# Softkey-bar.net
KiCad netlist of a schematic drawn in EAGLE
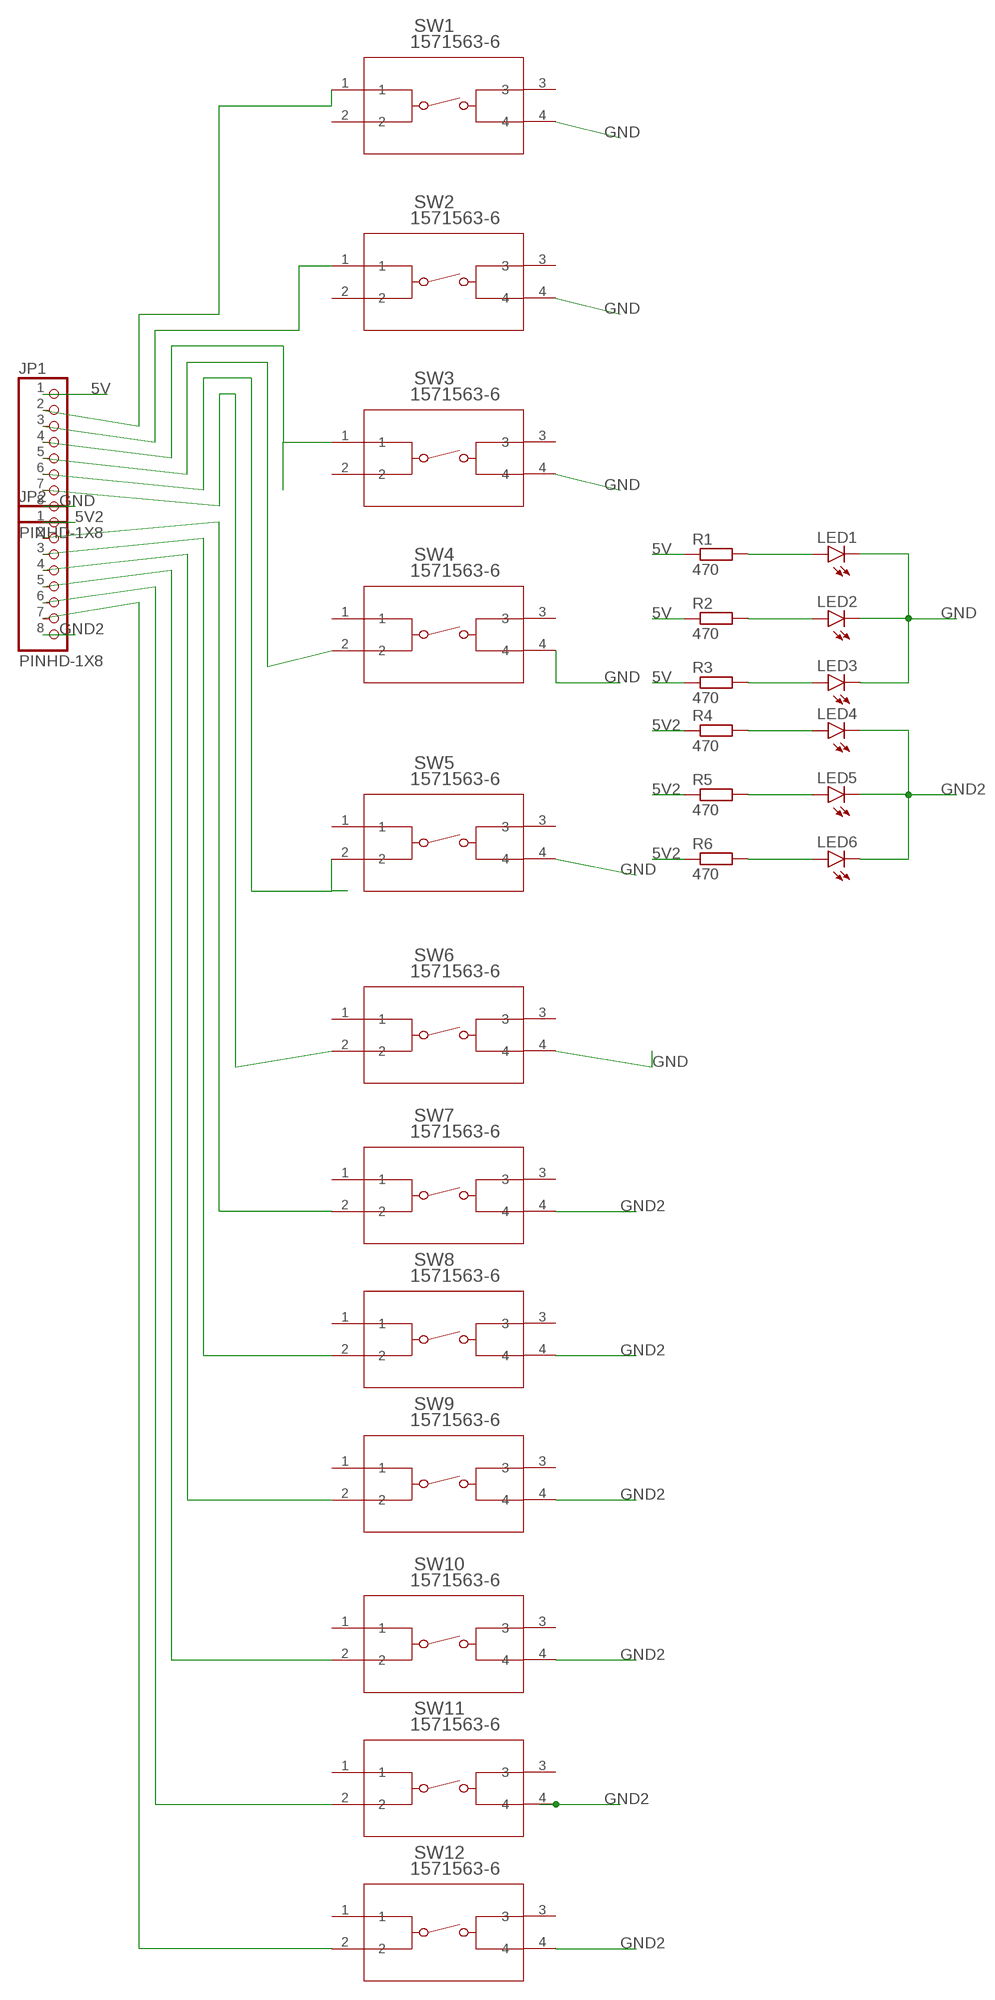
[diagram p0: schematic, sheet 1]

(export (version "E")
  (design (tool "Eeschema 10.0.6"))
  (components
    (comp (ref "JP1")
      (value "PINHD-1X8")
      (footprint "eagle-import:1X08")
      (libsource (lib "eagle-import") (part "PINHD-1X8"))
    )
    (comp (ref "JP2")
      (value "PINHD-1X8")
      (footprint "eagle-import:1X08")
      (libsource (lib "eagle-import") (part "PINHD-1X8"))
    )
    (comp (ref "LED1")
      (value "LEDCHIPLED_1206")
      (footprint "eagle-import:CHIPLED_1206")
      (libsource (lib "eagle-import") (part "LEDCHIPLED_1206"))
    )
    (comp (ref "LED2")
      (value "LEDCHIPLED_1206")
      (footprint "eagle-import:CHIPLED_1206")
      (libsource (lib "eagle-import") (part "LEDCHIPLED_1206"))
    )
    (comp (ref "LED3")
      (value "LEDCHIPLED_1206")
      (footprint "eagle-import:CHIPLED_1206")
      (libsource (lib "eagle-import") (part "LEDCHIPLED_1206"))
    )
    (comp (ref "LED4")
      (value "LEDCHIPLED_1206")
      (footprint "eagle-import:CHIPLED_1206")
      (libsource (lib "eagle-import") (part "LEDCHIPLED_1206"))
    )
    (comp (ref "LED5")
      (value "LEDCHIPLED_1206")
      (footprint "eagle-import:CHIPLED_1206")
      (libsource (lib "eagle-import") (part "LEDCHIPLED_1206"))
    )
    (comp (ref "LED6")
      (value "LEDCHIPLED_1206")
      (footprint "eagle-import:CHIPLED_1206")
      (libsource (lib "eagle-import") (part "LEDCHIPLED_1206"))
    )
    (comp (ref "R1")
      (value "470")
      (footprint "eagle-import:R0805")
      (libsource (lib "eagle-import") (part "R-EU_R0805"))
    )
    (comp (ref "R2")
      (value "470")
      (footprint "eagle-import:R0805")
      (libsource (lib "eagle-import") (part "R-EU_R0805"))
    )
    (comp (ref "R3")
      (value "470")
      (footprint "eagle-import:R0805")
      (libsource (lib "eagle-import") (part "R-EU_R0805"))
    )
    (comp (ref "R4")
      (value "470")
      (footprint "eagle-import:R0805")
      (libsource (lib "eagle-import") (part "R-EU_R0805"))
    )
    (comp (ref "R5")
      (value "470")
      (footprint "eagle-import:R0805")
      (libsource (lib "eagle-import") (part "R-EU_R0805"))
    )
    (comp (ref "R6")
      (value "470")
      (footprint "eagle-import:R0805")
      (libsource (lib "eagle-import") (part "R-EU_R0805"))
    )
    (comp (ref "SW1")
      (value "1571563-6")
      (footprint "eagle-import:SW4_1437565-E")
      (fields (field (name "COPYRIGHT") "Copyright (C) 2016 Accelerated Designs. All rights reserved"))
      (libsource (lib "eagle-import") (part "1571563-6"))
    )
    (comp (ref "SW2")
      (value "1571563-6")
      (footprint "eagle-import:SW4_1437565-E")
      (fields (field (name "COPYRIGHT") "Copyright (C) 2016 Accelerated Designs. All rights reserved"))
      (libsource (lib "eagle-import") (part "1571563-6"))
    )
    (comp (ref "SW3")
      (value "1571563-6")
      (footprint "eagle-import:SW4_1437565-E")
      (fields (field (name "COPYRIGHT") "Copyright (C) 2016 Accelerated Designs. All rights reserved"))
      (libsource (lib "eagle-import") (part "1571563-6"))
    )
    (comp (ref "SW4")
      (value "1571563-6")
      (footprint "eagle-import:SW4_1437565-E")
      (fields (field (name "COPYRIGHT") "Copyright (C) 2016 Accelerated Designs. All rights reserved"))
      (libsource (lib "eagle-import") (part "1571563-6"))
    )
    (comp (ref "SW5")
      (value "1571563-6")
      (footprint "eagle-import:SW4_1437565-E")
      (fields (field (name "COPYRIGHT") "Copyright (C) 2016 Accelerated Designs. All rights reserved"))
      (libsource (lib "eagle-import") (part "1571563-6"))
    )
    (comp (ref "SW6")
      (value "1571563-6")
      (footprint "eagle-import:SW4_1437565-E")
      (fields (field (name "COPYRIGHT") "Copyright (C) 2016 Accelerated Designs. All rights reserved"))
      (libsource (lib "eagle-import") (part "1571563-6"))
    )
    (comp (ref "SW7")
      (value "1571563-6")
      (footprint "eagle-import:SW4_1437565-E")
      (fields (field (name "COPYRIGHT") "Copyright (C) 2016 Accelerated Designs. All rights reserved"))
      (libsource (lib "eagle-import") (part "1571563-6"))
    )
    (comp (ref "SW8")
      (value "1571563-6")
      (footprint "eagle-import:SW4_1437565-E")
      (fields (field (name "COPYRIGHT") "Copyright (C) 2016 Accelerated Designs. All rights reserved"))
      (libsource (lib "eagle-import") (part "1571563-6"))
    )
    (comp (ref "SW9")
      (value "1571563-6")
      (footprint "eagle-import:SW4_1437565-E")
      (fields (field (name "COPYRIGHT") "Copyright (C) 2016 Accelerated Designs. All rights reserved"))
      (libsource (lib "eagle-import") (part "1571563-6"))
    )
    (comp (ref "SW10")
      (value "1571563-6")
      (footprint "eagle-import:SW4_1437565-E")
      (fields (field (name "COPYRIGHT") "Copyright (C) 2016 Accelerated Designs. All rights reserved"))
      (libsource (lib "eagle-import") (part "1571563-6"))
    )
    (comp (ref "SW11")
      (value "1571563-6")
      (footprint "eagle-import:SW4_1437565-E")
      (fields (field (name "COPYRIGHT") "Copyright (C) 2016 Accelerated Designs. All rights reserved"))
      (libsource (lib "eagle-import") (part "1571563-6"))
    )
    (comp (ref "SW12")
      (value "1571563-6")
      (footprint "eagle-import:SW4_1437565-E")
      (fields (field (name "COPYRIGHT") "Copyright (C) 2016 Accelerated Designs. All rights reserved"))
      (libsource (lib "eagle-import") (part "1571563-6"))
    )
  )
  (nets
    (net (code "1") (name "/5V") (class "Default")
      (node (ref "JP1") (pin "1") (pinfunction "1_1") (pintype "passive"))
      (node (ref "R1") (pin "1") (pinfunction "1_1") (pintype "passive"))
      (node (ref "R2") (pin "1") (pinfunction "1_1") (pintype "passive"))
      (node (ref "R3") (pin "1") (pinfunction "1_1") (pintype "passive"))
    )
    (net (code "2") (name "/5V2") (class "Default")
      (node (ref "JP2") (pin "1") (pinfunction "1_1") (pintype "passive"))
      (node (ref "R4") (pin "1") (pinfunction "1_1") (pintype "passive"))
      (node (ref "R5") (pin "1") (pinfunction "1_1") (pintype "passive"))
      (node (ref "R6") (pin "1") (pinfunction "1_1") (pintype "passive"))
    )
    (net (code "3") (name "/GND") (class "Default")
      (node (ref "JP1") (pin "8") (pinfunction "8_8") (pintype "passive"))
      (node (ref "LED1") (pin "C") (pinfunction "C_C") (pintype "passive"))
      (node (ref "LED2") (pin "C") (pinfunction "C_C") (pintype "passive"))
      (node (ref "LED3") (pin "C") (pinfunction "C_C") (pintype "passive"))
      (node (ref "SW1") (pin "4") (pinfunction "4_4") (pintype "passive"))
      (node (ref "SW2") (pin "4") (pinfunction "4_4") (pintype "passive"))
      (node (ref "SW3") (pin "4") (pinfunction "4_4") (pintype "passive"))
      (node (ref "SW4") (pin "4") (pinfunction "4_4") (pintype "passive"))
      (node (ref "SW5") (pin "4") (pinfunction "4_4") (pintype "passive"))
      (node (ref "SW6") (pin "4") (pinfunction "4_4") (pintype "passive"))
    )
    (net (code "4") (name "/GND2") (class "Default")
      (node (ref "JP2") (pin "8") (pinfunction "8_8") (pintype "passive"))
      (node (ref "LED4") (pin "C") (pinfunction "C_C") (pintype "passive"))
      (node (ref "LED5") (pin "C") (pinfunction "C_C") (pintype "passive"))
      (node (ref "LED6") (pin "C") (pinfunction "C_C") (pintype "passive"))
      (node (ref "SW10") (pin "4") (pinfunction "4_4") (pintype "passive"))
      (node (ref "SW11") (pin "4") (pinfunction "4_4") (pintype "passive"))
      (node (ref "SW12") (pin "4") (pinfunction "4_4") (pintype "passive"))
      (node (ref "SW7") (pin "4") (pinfunction "4_4") (pintype "passive"))
      (node (ref "SW8") (pin "4") (pinfunction "4_4") (pintype "passive"))
      (node (ref "SW9") (pin "4") (pinfunction "4_4") (pintype "passive"))
    )
    (net (code "5") (name "Net-(JP1-Pad2)") (class "Default")
      (node (ref "JP1") (pin "2") (pinfunction "2_2") (pintype "passive"))
      (node (ref "SW1") (pin "1") (pinfunction "1_1") (pintype "passive"))
    )
    (net (code "6") (name "Net-(JP1-Pad3)") (class "Default")
      (node (ref "JP1") (pin "3") (pinfunction "3_3") (pintype "passive"))
      (node (ref "SW2") (pin "1") (pinfunction "1_1") (pintype "passive"))
    )
    (net (code "7") (name "Net-(JP1-Pad4)") (class "Default")
      (node (ref "JP1") (pin "4") (pinfunction "4_4") (pintype "passive"))
      (node (ref "SW3") (pin "1") (pinfunction "1_1") (pintype "passive"))
    )
    (net (code "8") (name "Net-(JP1-Pad5)") (class "Default")
      (node (ref "JP1") (pin "5") (pinfunction "5_5") (pintype "passive"))
      (node (ref "SW4") (pin "2") (pinfunction "2_2") (pintype "passive"))
    )
    (net (code "9") (name "Net-(JP1-Pad6)") (class "Default")
      (node (ref "JP1") (pin "6") (pinfunction "6_6") (pintype "passive"))
      (node (ref "SW5") (pin "2") (pinfunction "2_2") (pintype "passive"))
    )
    (net (code "10") (name "Net-(JP1-Pad7)") (class "Default")
      (node (ref "JP1") (pin "7") (pinfunction "7_7") (pintype "passive"))
      (node (ref "SW6") (pin "2") (pinfunction "2_2") (pintype "passive"))
    )
    (net (code "11") (name "Net-(JP2-Pad2)") (class "Default")
      (node (ref "JP2") (pin "2") (pinfunction "2_2") (pintype "passive"))
      (node (ref "SW7") (pin "2") (pinfunction "2_2") (pintype "passive"))
    )
    (net (code "12") (name "Net-(JP2-Pad3)") (class "Default")
      (node (ref "JP2") (pin "3") (pinfunction "3_3") (pintype "passive"))
      (node (ref "SW8") (pin "2") (pinfunction "2_2") (pintype "passive"))
    )
    (net (code "13") (name "Net-(JP2-Pad4)") (class "Default")
      (node (ref "JP2") (pin "4") (pinfunction "4_4") (pintype "passive"))
      (node (ref "SW9") (pin "2") (pinfunction "2_2") (pintype "passive"))
    )
    (net (code "14") (name "Net-(JP2-Pad5)") (class "Default")
      (node (ref "JP2") (pin "5") (pinfunction "5_5") (pintype "passive"))
      (node (ref "SW10") (pin "2") (pinfunction "2_2") (pintype "passive"))
    )
    (net (code "15") (name "Net-(JP2-Pad6)") (class "Default")
      (node (ref "JP2") (pin "6") (pinfunction "6_6") (pintype "passive"))
      (node (ref "SW11") (pin "2") (pinfunction "2_2") (pintype "passive"))
    )
    (net (code "16") (name "Net-(JP2-Pad7)") (class "Default")
      (node (ref "JP2") (pin "7") (pinfunction "7_7") (pintype "passive"))
      (node (ref "SW12") (pin "2") (pinfunction "2_2") (pintype "passive"))
    )
    (net (code "17") (name "Net-(LED1-PadA)") (class "Default")
      (node (ref "LED1") (pin "A") (pinfunction "A_A") (pintype "passive"))
      (node (ref "R1") (pin "2") (pinfunction "2_2") (pintype "passive"))
    )
    (net (code "18") (name "Net-(LED2-PadA)") (class "Default")
      (node (ref "LED2") (pin "A") (pinfunction "A_A") (pintype "passive"))
      (node (ref "R2") (pin "2") (pinfunction "2_2") (pintype "passive"))
    )
    (net (code "19") (name "Net-(LED3-PadA)") (class "Default")
      (node (ref "LED3") (pin "A") (pinfunction "A_A") (pintype "passive"))
      (node (ref "R3") (pin "2") (pinfunction "2_2") (pintype "passive"))
    )
    (net (code "20") (name "Net-(LED4-PadA)") (class "Default")
      (node (ref "LED4") (pin "A") (pinfunction "A_A") (pintype "passive"))
      (node (ref "R4") (pin "2") (pinfunction "2_2") (pintype "passive"))
    )
    (net (code "21") (name "Net-(LED5-PadA)") (class "Default")
      (node (ref "LED5") (pin "A") (pinfunction "A_A") (pintype "passive"))
      (node (ref "R5") (pin "2") (pinfunction "2_2") (pintype "passive"))
    )
    (net (code "22") (name "Net-(LED6-PadA)") (class "Default")
      (node (ref "LED6") (pin "A") (pinfunction "A_A") (pintype "passive"))
      (node (ref "R6") (pin "2") (pinfunction "2_2") (pintype "passive"))
    )
    (net (code "23") (name "unconnected-(SW1-Pad2)") (class "Default")
      (node (ref "SW1") (pin "2") (pinfunction "2_2") (pintype "passive"))
    )
    (net (code "24") (name "unconnected-(SW1-Pad3)") (class "Default")
      (node (ref "SW1") (pin "3") (pinfunction "3_3") (pintype "passive"))
    )
    (net (code "25") (name "unconnected-(SW2-Pad2)") (class "Default")
      (node (ref "SW2") (pin "2") (pinfunction "2_2") (pintype "passive"))
    )
    (net (code "26") (name "unconnected-(SW2-Pad3)") (class "Default")
      (node (ref "SW2") (pin "3") (pinfunction "3_3") (pintype "passive"))
    )
    (net (code "27") (name "unconnected-(SW3-Pad2)") (class "Default")
      (node (ref "SW3") (pin "2") (pinfunction "2_2") (pintype "passive"))
    )
    (net (code "28") (name "unconnected-(SW3-Pad3)") (class "Default")
      (node (ref "SW3") (pin "3") (pinfunction "3_3") (pintype "passive"))
    )
    (net (code "29") (name "unconnected-(SW4-Pad1)") (class "Default")
      (node (ref "SW4") (pin "1") (pinfunction "1_1") (pintype "passive"))
    )
    (net (code "30") (name "unconnected-(SW4-Pad3)") (class "Default")
      (node (ref "SW4") (pin "3") (pinfunction "3_3") (pintype "passive"))
    )
    (net (code "31") (name "unconnected-(SW5-Pad1)") (class "Default")
      (node (ref "SW5") (pin "1") (pinfunction "1_1") (pintype "passive"))
    )
    (net (code "32") (name "unconnected-(SW5-Pad3)") (class "Default")
      (node (ref "SW5") (pin "3") (pinfunction "3_3") (pintype "passive"))
    )
    (net (code "33") (name "unconnected-(SW6-Pad1)") (class "Default")
      (node (ref "SW6") (pin "1") (pinfunction "1_1") (pintype "passive"))
    )
    (net (code "34") (name "unconnected-(SW6-Pad3)") (class "Default")
      (node (ref "SW6") (pin "3") (pinfunction "3_3") (pintype "passive"))
    )
    (net (code "35") (name "unconnected-(SW7-Pad1)") (class "Default")
      (node (ref "SW7") (pin "1") (pinfunction "1_1") (pintype "passive"))
    )
    (net (code "36") (name "unconnected-(SW7-Pad3)") (class "Default")
      (node (ref "SW7") (pin "3") (pinfunction "3_3") (pintype "passive"))
    )
    (net (code "37") (name "unconnected-(SW8-Pad1)") (class "Default")
      (node (ref "SW8") (pin "1") (pinfunction "1_1") (pintype "passive"))
    )
    (net (code "38") (name "unconnected-(SW8-Pad3)") (class "Default")
      (node (ref "SW8") (pin "3") (pinfunction "3_3") (pintype "passive"))
    )
    (net (code "39") (name "unconnected-(SW9-Pad1)") (class "Default")
      (node (ref "SW9") (pin "1") (pinfunction "1_1") (pintype "passive"))
    )
    (net (code "40") (name "unconnected-(SW9-Pad3)") (class "Default")
      (node (ref "SW9") (pin "3") (pinfunction "3_3") (pintype "passive"))
    )
    (net (code "41") (name "unconnected-(SW10-Pad1)") (class "Default")
      (node (ref "SW10") (pin "1") (pinfunction "1_1") (pintype "passive"))
    )
    (net (code "42") (name "unconnected-(SW10-Pad3)") (class "Default")
      (node (ref "SW10") (pin "3") (pinfunction "3_3") (pintype "passive"))
    )
    (net (code "43") (name "unconnected-(SW11-Pad1)") (class "Default")
      (node (ref "SW11") (pin "1") (pinfunction "1_1") (pintype "passive"))
    )
    (net (code "44") (name "unconnected-(SW11-Pad3)") (class "Default")
      (node (ref "SW11") (pin "3") (pinfunction "3_3") (pintype "passive"))
    )
    (net (code "45") (name "unconnected-(SW12-Pad1)") (class "Default")
      (node (ref "SW12") (pin "1") (pinfunction "1_1") (pintype "passive"))
    )
    (net (code "46") (name "unconnected-(SW12-Pad3)") (class "Default")
      (node (ref "SW12") (pin "3") (pinfunction "3_3") (pintype "passive"))
    )
  )
)
